# numishnik.net
KiCad netlist of a schematic drawn in EAGLE
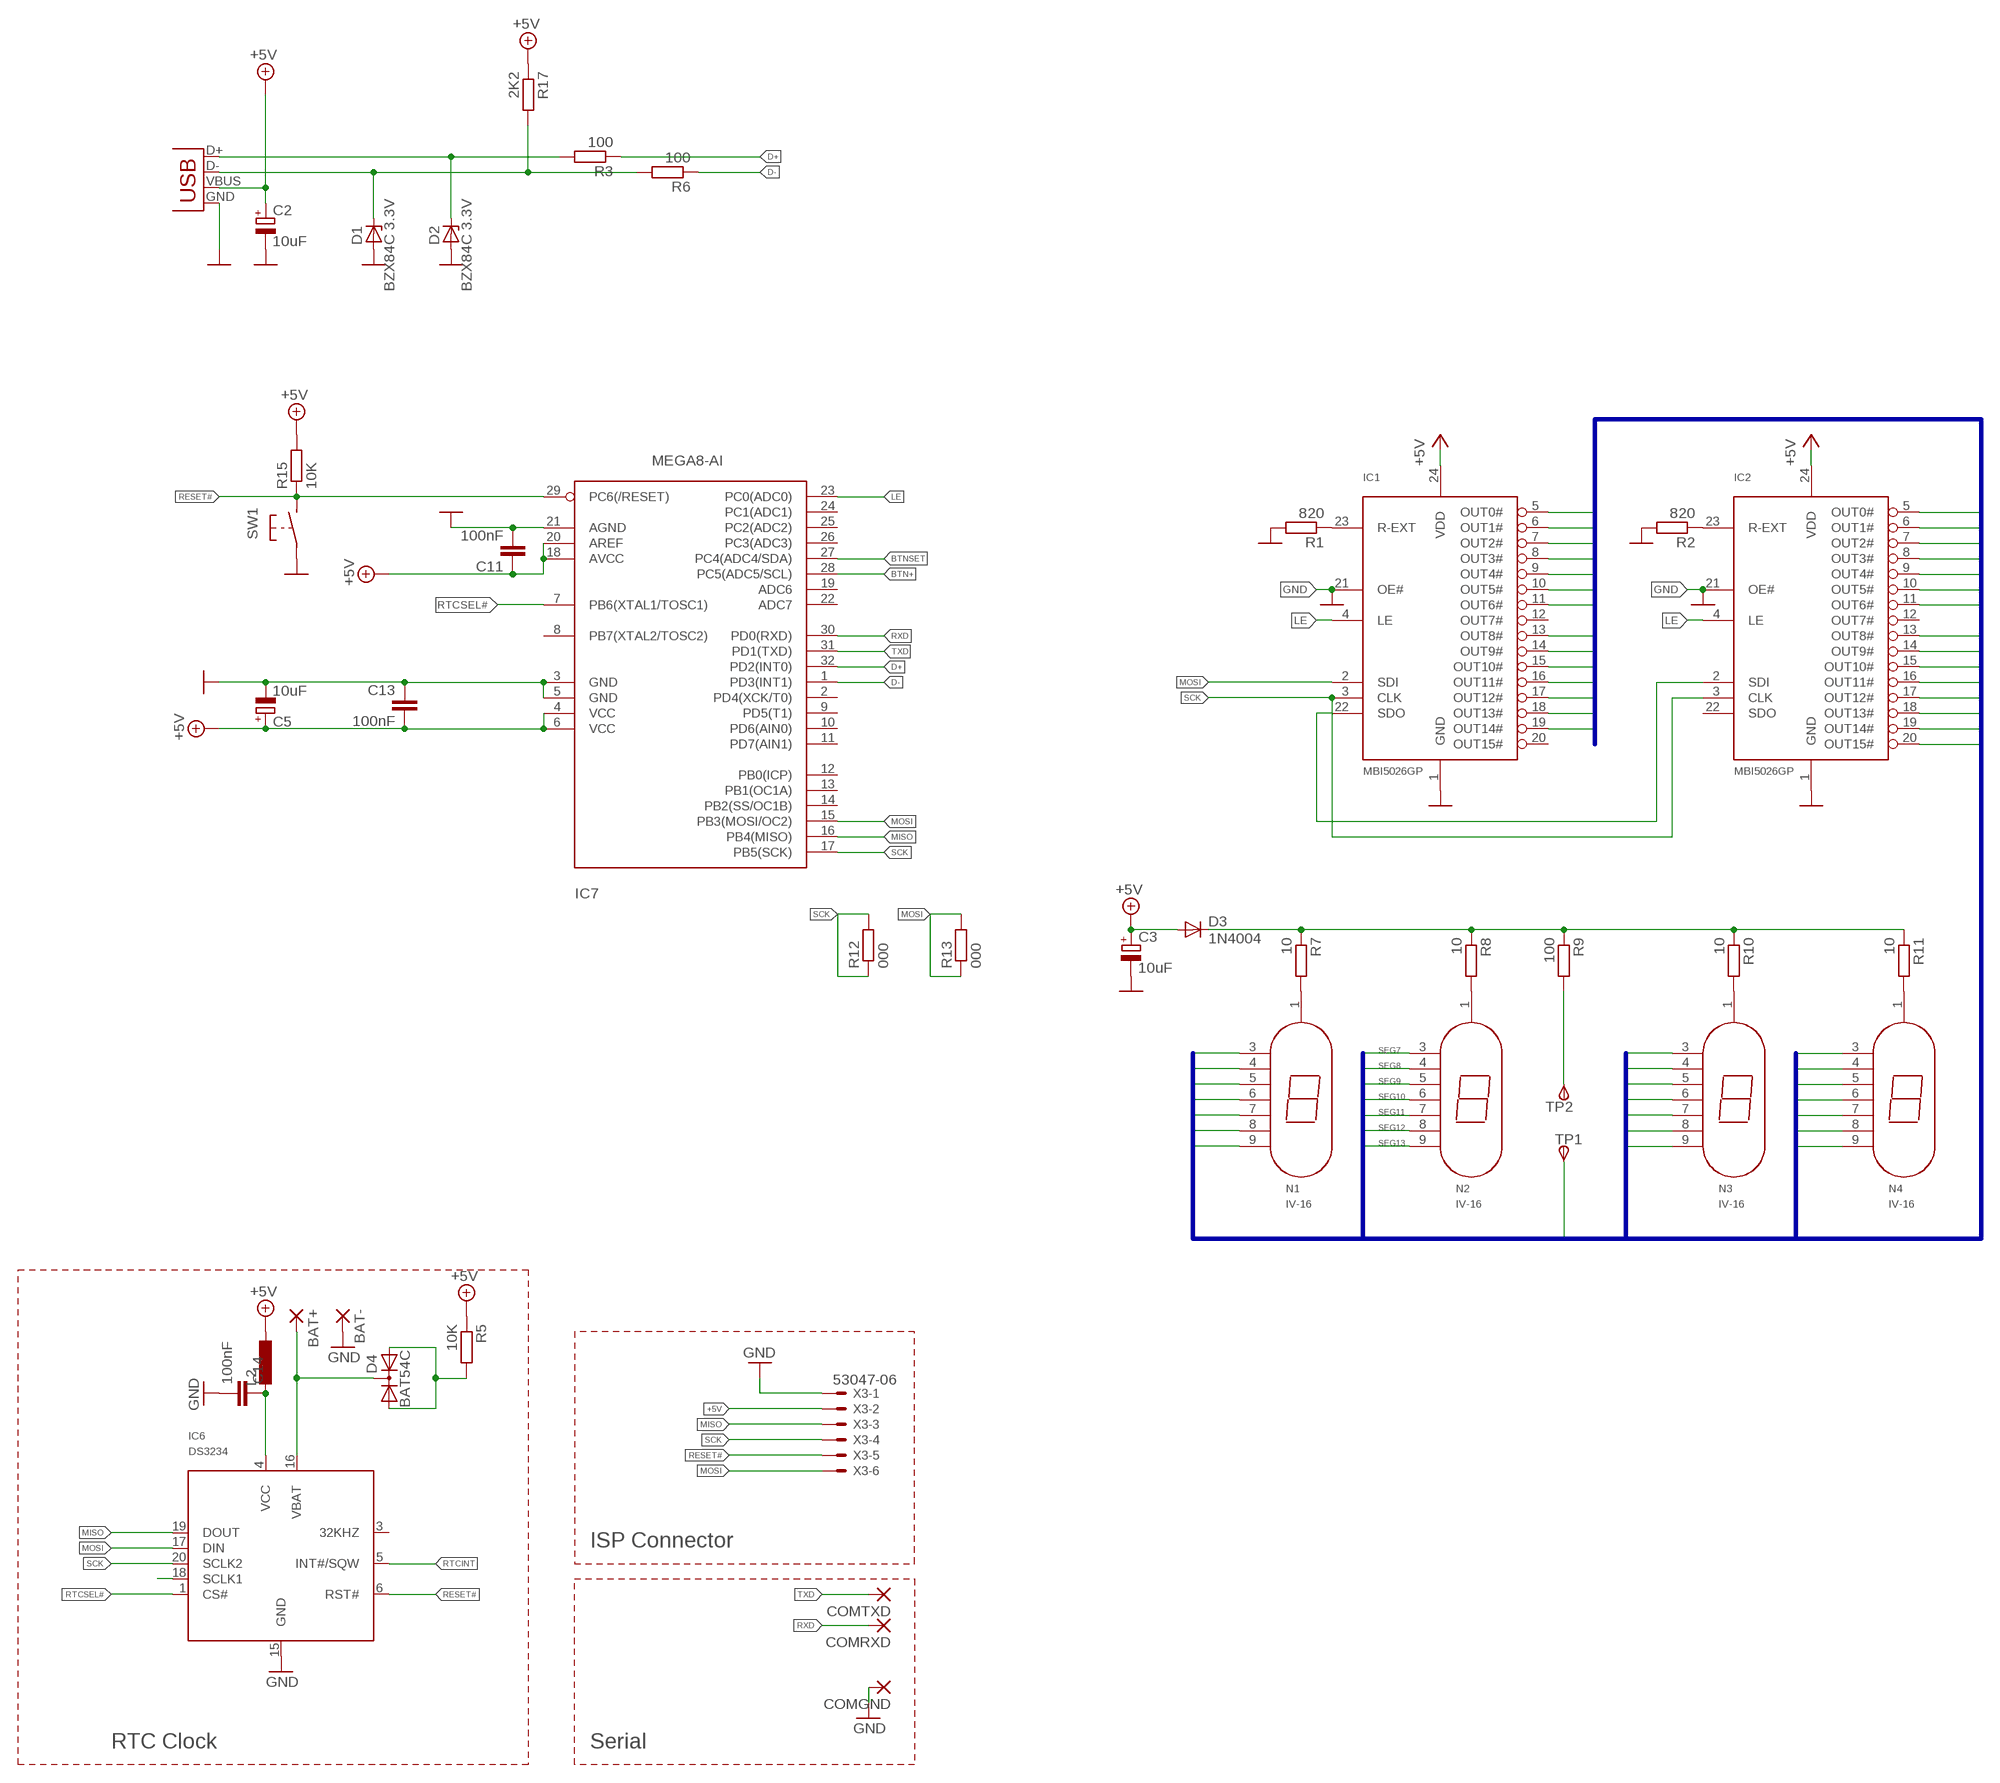
[diagram p0: schematic, sheet 1]

(export (version "E")
  (design (tool "Eeschema 10.0.6"))
  (components
    (comp (ref "BAT+")
      (value "1,6/0,8")
      (footprint "eagle-import:1,6_0,8")
      (libsource (lib "eagle-import") (part "1,6/0,8"))
    )
    (comp (ref "BAT-")
      (value "1,6/0,8")
      (footprint "eagle-import:1,6_0,8")
      (libsource (lib "eagle-import") (part "1,6/0,8"))
    )
    (comp (ref "C2")
      (value "10uF")
      (footprint "eagle-import:SMC_B")
      (libsource (lib "eagle-import") (part "CPOL-EUSMCB"))
    )
    (comp (ref "C3")
      (value "10uF")
      (footprint "eagle-import:SMC_B")
      (libsource (lib "eagle-import") (part "CPOL-EUSMCB"))
    )
    (comp (ref "C5")
      (value "10uF")
      (footprint "eagle-import:SMC_B")
      (libsource (lib "eagle-import") (part "CPOL-EUSMCB"))
    )
    (comp (ref "C11")
      (value "100nF")
      (footprint "eagle-import:C0603K")
      (libsource (lib "eagle-import") (part "C-EUC0603K"))
    )
    (comp (ref "C13")
      (value "100nF")
      (footprint "eagle-import:C0603K")
      (libsource (lib "eagle-import") (part "C-EUC0603K"))
    )
    (comp (ref "C14")
      (value "100nF")
      (footprint "eagle-import:C0603K")
      (libsource (lib "eagle-import") (part "C-EUC0603K"))
    )
    (comp (ref "COMGND")
      (value "1,6/0,8")
      (footprint "eagle-import:1,6_0,8")
      (libsource (lib "eagle-import") (part "1,6/0,8"))
    )
    (comp (ref "COMRXD")
      (value "1,6/0,8")
      (footprint "eagle-import:1,6_0,8")
      (libsource (lib "eagle-import") (part "1,6/0,8"))
    )
    (comp (ref "COMTXD")
      (value "1,6/0,8")
      (footprint "eagle-import:1,6_0,8")
      (libsource (lib "eagle-import") (part "1,6/0,8"))
    )
    (comp (ref "D1")
      (value "BZX84C 3.3V")
      (footprint "eagle-import:TO236")
      (libsource (lib "eagle-import") (part "BZX84CSMD"))
    )
    (comp (ref "D2")
      (value "BZX84C 3.3V")
      (footprint "eagle-import:TO236")
      (libsource (lib "eagle-import") (part "BZX84CSMD"))
    )
    (comp (ref "D3")
      (value "1N4004")
      (footprint "eagle-import:DO41-10")
      (libsource (lib "eagle-import") (part "1N4004"))
    )
    (comp (ref "D4")
      (value "BAT54C")
      (footprint "eagle-import:SOT23")
      (libsource (lib "eagle-import") (part "DIODE-2AC|CASOT23"))
    )
    (comp (ref "IC1")
      (value "MBI5026GP")
      (footprint "eagle-import:SSOP24-150")
      (libsource (lib "eagle-import") (part "MBI5026GP"))
    )
    (comp (ref "IC2")
      (value "MBI5026GP")
      (footprint "eagle-import:SSOP24-150")
      (libsource (lib "eagle-import") (part "MBI5026GP"))
    )
    (comp (ref "IC6")
      (value "DS3234")
      (footprint "eagle-import:SO-20DW")
      (libsource (lib "eagle-import") (part "DS3234"))
    )
    (comp (ref "IC7")
      (value "MEGA8-AI")
      (footprint "eagle-import:TQFP32-08")
      (libsource (lib "eagle-import") (part "MEGA8-AI"))
    )
    (comp (ref "L2")
      (value "L-EUL3230M")
      (footprint "eagle-import:L3230M")
      (libsource (lib "eagle-import") (part "L-EUL3230M"))
    )
    (comp (ref "N1")
      (value "IV-16")
      (footprint "eagle-import:IV-16")
      (libsource (lib "eagle-import") (part "IV-16"))
    )
    (comp (ref "N2")
      (value "IV-16")
      (footprint "eagle-import:IV-16")
      (libsource (lib "eagle-import") (part "IV-16"))
    )
    (comp (ref "N3")
      (value "IV-16")
      (footprint "eagle-import:IV-16")
      (libsource (lib "eagle-import") (part "IV-16"))
    )
    (comp (ref "N4")
      (value "IV-16")
      (footprint "eagle-import:IV-16")
      (libsource (lib "eagle-import") (part "IV-16"))
    )
    (comp (ref "R1")
      (value "820")
      (footprint "eagle-import:R0805-SVO")
      (libsource (lib "eagle-import") (part "R-EU_R0805S"))
    )
    (comp (ref "R2")
      (value "820")
      (footprint "eagle-import:R0805-SVO")
      (libsource (lib "eagle-import") (part "R-EU_R0805S"))
    )
    (comp (ref "R3")
      (value "100")
      (footprint "eagle-import:R0805-SVO")
      (libsource (lib "eagle-import") (part "R-EU_R0805S"))
    )
    (comp (ref "R5")
      (value "10K")
      (footprint "eagle-import:R0805-SVO")
      (libsource (lib "eagle-import") (part "R-EU_R0805S"))
    )
    (comp (ref "R6")
      (value "100")
      (footprint "eagle-import:R0805-SVO")
      (libsource (lib "eagle-import") (part "R-EU_R0805S"))
    )
    (comp (ref "R7")
      (value "10")
      (footprint "eagle-import:R0805-SVO")
      (libsource (lib "eagle-import") (part "R-EU_R0805S"))
    )
    (comp (ref "R8")
      (value "10")
      (footprint "eagle-import:R0805-SVO")
      (libsource (lib "eagle-import") (part "R-EU_R0805S"))
    )
    (comp (ref "R9")
      (value "100")
      (footprint "eagle-import:R0805-SVO")
      (libsource (lib "eagle-import") (part "R-EU_R0805S"))
    )
    (comp (ref "R10")
      (value "10")
      (footprint "eagle-import:R0805-SVO")
      (libsource (lib "eagle-import") (part "R-EU_R0805S"))
    )
    (comp (ref "R11")
      (value "10")
      (footprint "eagle-import:R0805-SVO")
      (libsource (lib "eagle-import") (part "R-EU_R0805S"))
    )
    (comp (ref "R12")
      (value "000")
      (footprint "eagle-import:R0805-SVO")
      (libsource (lib "eagle-import") (part "R-EU_R0805S"))
    )
    (comp (ref "R13")
      (value "000")
      (footprint "eagle-import:R0805-SVO")
      (libsource (lib "eagle-import") (part "R-EU_R0805S"))
    )
    (comp (ref "R15")
      (value "10K")
      (footprint "eagle-import:R0805-SVO")
      (libsource (lib "eagle-import") (part "R-EU_R0805S"))
    )
    (comp (ref "R17")
      (value "2K2")
      (footprint "eagle-import:R0805-SVO")
      (libsource (lib "eagle-import") (part "R-EU_R0805S"))
    )
    (comp (ref "SW1")
      (value "BUTTON-IT_1181")
      (footprint "eagle-import:SW_IT1181")
      (libsource (lib "eagle-import") (part "BUTTON-IT_1181"))
    )
    (comp (ref "TP1")
      (value "TPSPAD1-13")
      (footprint "eagle-import:P1-13")
      (libsource (lib "eagle-import") (part "TPSPAD1-13"))
    )
    (comp (ref "TP2")
      (value "TPSPAD1-13")
      (footprint "eagle-import:P1-13")
      (libsource (lib "eagle-import") (part "TPSPAD1-13"))
    )
    (comp (ref "X1")
      (value "USB-MICROB")
      (footprint "eagle-import:USB-MICROB")
      (libsource (lib "eagle-import") (part "USB-MICROB"))
    )
    (comp (ref "X3")
      (value "53047-06")
      (footprint "eagle-import:53047-06")
      (libsource (lib "eagle-import") (part "53?-06047"))
    )
  )
  (nets
    (net (code "1") (name "+5V") (class "Default")
      (node (ref "C11") (pin "1") (pinfunction "1_1") (pintype "passive"))
      (node (ref "C13") (pin "2") (pinfunction "2_2") (pintype "passive"))
      (node (ref "C2") (pin "+") (pinfunction "+_+") (pintype "passive"))
      (node (ref "C3") (pin "+") (pinfunction "+_+") (pintype "passive"))
      (node (ref "C5") (pin "+") (pinfunction "+_+") (pintype "passive"))
      (node (ref "D3") (pin "A") (pinfunction "A_A") (pintype "passive"))
      (node (ref "IC1") (pin "24") (pinfunction "VDD_24") (pintype "power_in"))
      (node (ref "IC2") (pin "24") (pinfunction "VDD_24") (pintype "power_in"))
      (node (ref "IC7") (pin "18") (pinfunction "AVCC_18") (pintype "power_in"))
      (node (ref "IC7") (pin "20") (pinfunction "AREF_20") (pintype "passive"))
      (node (ref "IC7") (pin "4") (pinfunction "VCC_4") (pintype "power_in"))
      (node (ref "IC7") (pin "6") (pinfunction "VCC_6") (pintype "power_in"))
      (node (ref "L2") (pin "1") (pinfunction "1_1") (pintype "passive"))
      (node (ref "R15") (pin "2") (pinfunction "2_2") (pintype "passive"))
      (node (ref "R17") (pin "1") (pinfunction "1_1") (pintype "passive"))
      (node (ref "R5") (pin "1") (pinfunction "1_1") (pintype "passive"))
      (node (ref "X1") (pin "VBUS") (pinfunction "VBUS_VBUS") (pintype "bidirectional"))
      (node (ref "X3") (pin "2") (pinfunction "S_2") (pintype "passive"))
    )
    (net (code "2") (name "/DOT") (class "Default")
      (node (ref "IC2") (pin "20") (pinfunction "OUT15#_20") (pintype "bidirectional"))
      (node (ref "TP1") (pin "1") (pinfunction "PP_1") (pintype "input"))
    )
    (net (code "3") (name "/SEG0") (class "Default")
      (node (ref "IC1") (pin "11") (pinfunction "OUT6#_11") (pintype "bidirectional"))
      (node (ref "N1") (pin "3") (pinfunction "2_3") (pintype "bidirectional"))
    )
    (net (code "4") (name "/SEG1") (class "Default")
      (node (ref "IC1") (pin "10") (pinfunction "OUT5#_10") (pintype "bidirectional"))
      (node (ref "N1") (pin "4") (pinfunction "3_4") (pintype "bidirectional"))
    )
    (net (code "5") (name "/SEG2") (class "Default")
      (node (ref "IC1") (pin "9") (pinfunction "OUT4#_9") (pintype "bidirectional"))
      (node (ref "N1") (pin "5") (pinfunction "4_5") (pintype "bidirectional"))
    )
    (net (code "6") (name "/SEG3") (class "Default")
      (node (ref "IC1") (pin "8") (pinfunction "OUT3#_8") (pintype "bidirectional"))
      (node (ref "N1") (pin "6") (pinfunction "5_6") (pintype "bidirectional"))
    )
    (net (code "7") (name "/SEG4") (class "Default")
      (node (ref "IC1") (pin "7") (pinfunction "OUT2#_7") (pintype "bidirectional"))
      (node (ref "N1") (pin "7") (pinfunction "6_7") (pintype "bidirectional"))
    )
    (net (code "8") (name "/SEG5") (class "Default")
      (node (ref "IC1") (pin "6") (pinfunction "OUT1#_6") (pintype "bidirectional"))
      (node (ref "N1") (pin "8") (pinfunction "7_8") (pintype "bidirectional"))
    )
    (net (code "9") (name "/SEG6") (class "Default")
      (node (ref "IC1") (pin "5") (pinfunction "OUT0#_5") (pintype "bidirectional"))
      (node (ref "N1") (pin "9") (pinfunction "8_9") (pintype "bidirectional"))
    )
    (net (code "10") (name "/SEG7") (class "Default")
      (node (ref "IC1") (pin "19") (pinfunction "OUT14#_19") (pintype "bidirectional"))
      (node (ref "N2") (pin "3") (pinfunction "2_3") (pintype "bidirectional"))
    )
    (net (code "11") (name "/SEG8") (class "Default")
      (node (ref "IC1") (pin "18") (pinfunction "OUT13#_18") (pintype "bidirectional"))
      (node (ref "N2") (pin "4") (pinfunction "3_4") (pintype "bidirectional"))
    )
    (net (code "12") (name "/SEG9") (class "Default")
      (node (ref "IC1") (pin "17") (pinfunction "OUT12#_17") (pintype "bidirectional"))
      (node (ref "N2") (pin "5") (pinfunction "4_5") (pintype "bidirectional"))
    )
    (net (code "13") (name "/SEG10") (class "Default")
      (node (ref "IC1") (pin "16") (pinfunction "OUT11#_16") (pintype "bidirectional"))
      (node (ref "N2") (pin "6") (pinfunction "5_6") (pintype "bidirectional"))
    )
    (net (code "14") (name "/SEG11") (class "Default")
      (node (ref "IC1") (pin "15") (pinfunction "OUT10#_15") (pintype "bidirectional"))
      (node (ref "N2") (pin "7") (pinfunction "6_7") (pintype "bidirectional"))
    )
    (net (code "15") (name "/SEG12") (class "Default")
      (node (ref "IC1") (pin "14") (pinfunction "OUT9#_14") (pintype "bidirectional"))
      (node (ref "N2") (pin "8") (pinfunction "7_8") (pintype "bidirectional"))
    )
    (net (code "16") (name "/SEG13") (class "Default")
      (node (ref "IC1") (pin "13") (pinfunction "OUT8#_13") (pintype "bidirectional"))
      (node (ref "N2") (pin "9") (pinfunction "8_9") (pintype "bidirectional"))
    )
    (net (code "17") (name "/SEG14") (class "Default")
      (node (ref "IC2") (pin "11") (pinfunction "OUT6#_11") (pintype "bidirectional"))
      (node (ref "N3") (pin "3") (pinfunction "2_3") (pintype "bidirectional"))
    )
    (net (code "18") (name "/SEG15") (class "Default")
      (node (ref "IC2") (pin "10") (pinfunction "OUT5#_10") (pintype "bidirectional"))
      (node (ref "N3") (pin "4") (pinfunction "3_4") (pintype "bidirectional"))
    )
    (net (code "19") (name "/SEG16") (class "Default")
      (node (ref "IC2") (pin "9") (pinfunction "OUT4#_9") (pintype "bidirectional"))
      (node (ref "N3") (pin "5") (pinfunction "4_5") (pintype "bidirectional"))
    )
    (net (code "20") (name "/SEG17") (class "Default")
      (node (ref "IC2") (pin "8") (pinfunction "OUT3#_8") (pintype "bidirectional"))
      (node (ref "N3") (pin "6") (pinfunction "5_6") (pintype "bidirectional"))
    )
    (net (code "21") (name "/SEG18") (class "Default")
      (node (ref "IC2") (pin "7") (pinfunction "OUT2#_7") (pintype "bidirectional"))
      (node (ref "N3") (pin "7") (pinfunction "6_7") (pintype "bidirectional"))
    )
    (net (code "22") (name "/SEG19") (class "Default")
      (node (ref "IC2") (pin "6") (pinfunction "OUT1#_6") (pintype "bidirectional"))
      (node (ref "N3") (pin "8") (pinfunction "7_8") (pintype "bidirectional"))
    )
    (net (code "23") (name "/SEG20") (class "Default")
      (node (ref "IC2") (pin "5") (pinfunction "OUT0#_5") (pintype "bidirectional"))
      (node (ref "N3") (pin "9") (pinfunction "8_9") (pintype "bidirectional"))
    )
    (net (code "24") (name "/SEG21") (class "Default")
      (node (ref "IC2") (pin "19") (pinfunction "OUT14#_19") (pintype "bidirectional"))
      (node (ref "N4") (pin "3") (pinfunction "2_3") (pintype "bidirectional"))
    )
    (net (code "25") (name "/SEG22") (class "Default")
      (node (ref "IC2") (pin "18") (pinfunction "OUT13#_18") (pintype "bidirectional"))
      (node (ref "N4") (pin "4") (pinfunction "3_4") (pintype "bidirectional"))
    )
    (net (code "26") (name "/SEG23") (class "Default")
      (node (ref "IC2") (pin "17") (pinfunction "OUT12#_17") (pintype "bidirectional"))
      (node (ref "N4") (pin "5") (pinfunction "4_5") (pintype "bidirectional"))
    )
    (net (code "27") (name "/SEG24") (class "Default")
      (node (ref "IC2") (pin "16") (pinfunction "OUT11#_16") (pintype "bidirectional"))
      (node (ref "N4") (pin "6") (pinfunction "5_6") (pintype "bidirectional"))
    )
    (net (code "28") (name "/SEG25") (class "Default")
      (node (ref "IC2") (pin "15") (pinfunction "OUT10#_15") (pintype "bidirectional"))
      (node (ref "N4") (pin "7") (pinfunction "6_7") (pintype "bidirectional"))
    )
    (net (code "29") (name "/SEG26") (class "Default")
      (node (ref "IC2") (pin "14") (pinfunction "OUT9#_14") (pintype "bidirectional"))
      (node (ref "N4") (pin "8") (pinfunction "7_8") (pintype "bidirectional"))
    )
    (net (code "30") (name "/SEG27") (class "Default")
      (node (ref "IC2") (pin "13") (pinfunction "OUT8#_13") (pintype "bidirectional"))
      (node (ref "N4") (pin "9") (pinfunction "8_9") (pintype "bidirectional"))
    )
    (net (code "31") (name "BTN+") (class "Default")
      (node (ref "IC7") (pin "28") (pinfunction "PC5(ADC5/SCL)_28") (pintype "bidirectional"))
    )
    (net (code "32") (name "BTNSET") (class "Default")
      (node (ref "IC7") (pin "27") (pinfunction "PC4(ADC4/SDA)_27") (pintype "bidirectional"))
    )
    (net (code "33") (name "D+") (class "Default")
      (node (ref "IC7") (pin "32") (pinfunction "PD2(INT0)_32") (pintype "bidirectional"))
      (node (ref "R3") (pin "1") (pinfunction "1_1") (pintype "passive"))
    )
    (net (code "34") (name "D-") (class "Default")
      (node (ref "IC7") (pin "1") (pinfunction "PD3(INT1)_1") (pintype "bidirectional"))
      (node (ref "R6") (pin "1") (pinfunction "1_1") (pintype "passive"))
    )
    (net (code "35") (name "GND") (class "Default")
      (node (ref "BAT-") (pin "1") (pinfunction "P_1") (pintype "passive"))
      (node (ref "C11") (pin "2") (pinfunction "2_2") (pintype "passive"))
      (node (ref "C13") (pin "1") (pinfunction "1_1") (pintype "passive"))
      (node (ref "C14") (pin "2") (pinfunction "2_2") (pintype "passive"))
      (node (ref "C2") (pin "-") (pinfunction "-_-") (pintype "passive"))
      (node (ref "C3") (pin "-") (pinfunction "-_-") (pintype "passive"))
      (node (ref "C5") (pin "-") (pinfunction "-_-") (pintype "passive"))
      (node (ref "COMGND") (pin "1") (pinfunction "P_1") (pintype "passive"))
      (node (ref "D1") (pin "A") (pinfunction "A_A") (pintype "passive"))
      (node (ref "D2") (pin "A") (pinfunction "A_A") (pintype "passive"))
      (node (ref "IC1") (pin "1") (pinfunction "GND_1") (pintype "power_in"))
      (node (ref "IC1") (pin "21") (pinfunction "OE#_21") (pintype "bidirectional"))
      (node (ref "IC2") (pin "1") (pinfunction "GND_1") (pintype "power_in"))
      (node (ref "IC2") (pin "21") (pinfunction "OE#_21") (pintype "bidirectional"))
      (node (ref "IC6") (pin "15") (pinfunction "GND_15") (pintype "bidirectional"))
      (node (ref "IC7") (pin "21") (pinfunction "AGND_21") (pintype "power_in"))
      (node (ref "IC7") (pin "3") (pinfunction "GND_3") (pintype "power_in"))
      (node (ref "IC7") (pin "5") (pinfunction "GND_5") (pintype "power_in"))
      (node (ref "R1") (pin "2") (pinfunction "2_2") (pintype "passive"))
      (node (ref "R2") (pin "2") (pinfunction "2_2") (pintype "passive"))
      (node (ref "SW1") (pin "P$1") (pinfunction "P1_P$1") (pintype "passive"))
      (node (ref "X1") (pin "GND") (pinfunction "GND_GND") (pintype "bidirectional"))
      (node (ref "X3") (pin "1") (pinfunction "S_1") (pintype "passive"))
    )
    (net (code "36") (name "LE") (class "Default")
      (node (ref "IC1") (pin "4") (pinfunction "LE_4") (pintype "bidirectional"))
      (node (ref "IC2") (pin "4") (pinfunction "LE_4") (pintype "bidirectional"))
      (node (ref "IC7") (pin "23") (pinfunction "PC0(ADC0)_23") (pintype "bidirectional"))
    )
    (net (code "37") (name "MISO") (class "Default")
      (node (ref "IC6") (pin "19") (pinfunction "DOUT_19") (pintype "bidirectional"))
      (node (ref "IC7") (pin "16") (pinfunction "PB4(MISO)_16") (pintype "bidirectional"))
      (node (ref "X3") (pin "3") (pinfunction "S_3") (pintype "passive"))
    )
    (net (code "38") (name "MOSI") (class "Default")
      (node (ref "IC1") (pin "2") (pinfunction "SDI_2") (pintype "bidirectional"))
      (node (ref "IC6") (pin "17") (pinfunction "DIN_17") (pintype "bidirectional"))
      (node (ref "IC7") (pin "15") (pinfunction "PB3(MOSI/OC2)_15") (pintype "bidirectional"))
      (node (ref "R13") (pin "1") (pinfunction "1_1") (pintype "passive"))
      (node (ref "R13") (pin "2") (pinfunction "2_2") (pintype "passive"))
      (node (ref "X3") (pin "6") (pinfunction "S_6") (pintype "passive"))
    )
    (net (code "39") (name "Net-(BAT+-P)") (class "Default")
      (node (ref "BAT+") (pin "1") (pinfunction "P_1") (pintype "passive"))
      (node (ref "D4") (pin "3") (pinfunction "C_3") (pintype "passive"))
      (node (ref "IC6") (pin "16") (pinfunction "VBAT_16") (pintype "bidirectional"))
    )
    (net (code "40") (name "Net-(D1-PadC)") (class "Default")
      (node (ref "D1") (pin "C") (pinfunction "C_C") (pintype "passive"))
      (node (ref "R17") (pin "2") (pinfunction "2_2") (pintype "passive"))
      (node (ref "R6") (pin "2") (pinfunction "2_2") (pintype "passive"))
      (node (ref "X1") (pin "D-") (pinfunction "D-_D-") (pintype "bidirectional"))
    )
    (net (code "41") (name "Net-(D2-PadC)") (class "Default")
      (node (ref "D2") (pin "C") (pinfunction "C_C") (pintype "passive"))
      (node (ref "R3") (pin "2") (pinfunction "2_2") (pintype "passive"))
      (node (ref "X1") (pin "D+") (pinfunction "D+_D+") (pintype "bidirectional"))
    )
    (net (code "42") (name "Net-(D3-PadC)") (class "Default")
      (node (ref "D3") (pin "C") (pinfunction "C_C") (pintype "passive"))
      (node (ref "R10") (pin "1") (pinfunction "1_1") (pintype "passive"))
      (node (ref "R11") (pin "1") (pinfunction "1_1") (pintype "passive"))
      (node (ref "R7") (pin "1") (pinfunction "1_1") (pintype "passive"))
      (node (ref "R8") (pin "1") (pinfunction "1_1") (pintype "passive"))
      (node (ref "R9") (pin "1") (pinfunction "1_1") (pintype "passive"))
    )
    (net (code "43") (name "Net-(D4-A1)") (class "Default")
      (node (ref "D4") (pin "1") (pinfunction "A1_1") (pintype "passive"))
      (node (ref "D4") (pin "2") (pinfunction "A2_2") (pintype "passive"))
      (node (ref "R5") (pin "2") (pinfunction "2_2") (pintype "passive"))
    )
    (net (code "44") (name "Net-(IC1-R-EXT)") (class "Default")
      (node (ref "IC1") (pin "23") (pinfunction "R-EXT_23") (pintype "bidirectional"))
      (node (ref "R1") (pin "1") (pinfunction "1_1") (pintype "passive"))
    )
    (net (code "45") (name "Net-(IC1-SDO)") (class "Default")
      (node (ref "IC1") (pin "22") (pinfunction "SDO_22") (pintype "bidirectional"))
      (node (ref "IC2") (pin "2") (pinfunction "SDI_2") (pintype "bidirectional"))
    )
    (net (code "46") (name "Net-(IC2-R-EXT)") (class "Default")
      (node (ref "IC2") (pin "23") (pinfunction "R-EXT_23") (pintype "bidirectional"))
      (node (ref "R2") (pin "1") (pinfunction "1_1") (pintype "passive"))
    )
    (net (code "47") (name "Net-(IC6-VCC)") (class "Default")
      (node (ref "C14") (pin "1") (pinfunction "1_1") (pintype "passive"))
      (node (ref "IC6") (pin "4") (pinfunction "VCC_4") (pintype "bidirectional"))
      (node (ref "L2") (pin "2") (pinfunction "2_2") (pintype "passive"))
    )
    (net (code "48") (name "Net-(N1-Pad1)") (class "Default")
      (node (ref "N1") (pin "1") (pinfunction "1_1") (pintype "bidirectional"))
      (node (ref "R7") (pin "2") (pinfunction "2_2") (pintype "passive"))
    )
    (net (code "49") (name "Net-(N2-Pad1)") (class "Default")
      (node (ref "N2") (pin "1") (pinfunction "1_1") (pintype "bidirectional"))
      (node (ref "R8") (pin "2") (pinfunction "2_2") (pintype "passive"))
    )
    (net (code "50") (name "Net-(N3-Pad1)") (class "Default")
      (node (ref "N3") (pin "1") (pinfunction "1_1") (pintype "bidirectional"))
      (node (ref "R10") (pin "2") (pinfunction "2_2") (pintype "passive"))
    )
    (net (code "51") (name "Net-(N4-Pad1)") (class "Default")
      (node (ref "N4") (pin "1") (pinfunction "1_1") (pintype "bidirectional"))
      (node (ref "R11") (pin "2") (pinfunction "2_2") (pintype "passive"))
    )
    (net (code "52") (name "Net-(TP2-PP)") (class "Default")
      (node (ref "R9") (pin "2") (pinfunction "2_2") (pintype "passive"))
      (node (ref "TP2") (pin "1") (pinfunction "PP_1") (pintype "input"))
    )
    (net (code "53") (name "RESET#") (class "Default")
      (node (ref "IC6") (pin "6") (pinfunction "RST#_6") (pintype "bidirectional"))
      (node (ref "IC7") (pin "29") (pinfunction "PC6(/RESET)_29") (pintype "bidirectional"))
      (node (ref "R15") (pin "1") (pinfunction "1_1") (pintype "passive"))
      (node (ref "SW1") (pin "P$2") (pinfunction "P2_P$2") (pintype "passive"))
      (node (ref "X3") (pin "5") (pinfunction "S_5") (pintype "passive"))
    )
    (net (code "54") (name "RTCINT") (class "Default")
      (node (ref "IC6") (pin "5") (pinfunction "INT#/SQW_5") (pintype "bidirectional"))
    )
    (net (code "55") (name "RTCSEL#") (class "Default")
      (node (ref "IC6") (pin "1") (pinfunction "CS#_1") (pintype "bidirectional"))
      (node (ref "IC7") (pin "7") (pinfunction "PB6(XTAL1/TOSC1)_7") (pintype "bidirectional"))
    )
    (net (code "56") (name "RXD") (class "Default")
      (node (ref "COMRXD") (pin "1") (pinfunction "P_1") (pintype "passive"))
      (node (ref "IC7") (pin "30") (pinfunction "PD0(RXD)_30") (pintype "bidirectional"))
    )
    (net (code "57") (name "SCK") (class "Default")
      (node (ref "IC1") (pin "3") (pinfunction "CLK_3") (pintype "bidirectional"))
      (node (ref "IC2") (pin "3") (pinfunction "CLK_3") (pintype "bidirectional"))
      (node (ref "IC6") (pin "20") (pinfunction "SCLK2_20") (pintype "bidirectional"))
      (node (ref "IC7") (pin "17") (pinfunction "PB5(SCK)_17") (pintype "bidirectional"))
      (node (ref "R12") (pin "1") (pinfunction "1_1") (pintype "passive"))
      (node (ref "R12") (pin "2") (pinfunction "2_2") (pintype "passive"))
      (node (ref "X3") (pin "4") (pinfunction "S_4") (pintype "passive"))
    )
    (net (code "58") (name "TXD") (class "Default")
      (node (ref "COMTXD") (pin "1") (pinfunction "P_1") (pintype "passive"))
      (node (ref "IC7") (pin "31") (pinfunction "PD1(TXD)_31") (pintype "bidirectional"))
    )
    (net (code "59") (name "unconnected-(IC1-OUT7#-Pad12)") (class "Default")
      (node (ref "IC1") (pin "12") (pinfunction "OUT7#_12") (pintype "bidirectional"))
    )
    (net (code "60") (name "unconnected-(IC1-OUT15#-Pad20)") (class "Default")
      (node (ref "IC1") (pin "20") (pinfunction "OUT15#_20") (pintype "bidirectional"))
    )
    (net (code "61") (name "unconnected-(IC2-OUT7#-Pad12)") (class "Default")
      (node (ref "IC2") (pin "12") (pinfunction "OUT7#_12") (pintype "bidirectional"))
    )
    (net (code "62") (name "unconnected-(IC2-SDO-Pad22)") (class "Default")
      (node (ref "IC2") (pin "22") (pinfunction "SDO_22") (pintype "bidirectional"))
    )
    (net (code "63") (name "unconnected-(IC6-32KHZ-Pad3)") (class "Default")
      (node (ref "IC6") (pin "3") (pinfunction "32KHZ_3") (pintype "bidirectional"))
    )
    (net (code "64") (name "unconnected-(IC6-SCLK1-Pad18)") (class "Default")
      (node (ref "IC6") (pin "18") (pinfunction "SCLK1_18") (pintype "bidirectional"))
    )
    (net (code "65") (name "unconnected-(IC7-ADC6-Pad19)") (class "Default")
      (node (ref "IC7") (pin "19") (pinfunction "ADC6_19") (pintype "bidirectional"))
    )
    (net (code "66") (name "unconnected-(IC7-ADC7-Pad22)") (class "Default")
      (node (ref "IC7") (pin "22") (pinfunction "ADC7_22") (pintype "bidirectional"))
    )
    (net (code "67") (name "unconnected-(IC7-PB0(ICP)-Pad12)") (class "Default")
      (node (ref "IC7") (pin "12") (pinfunction "PB0(ICP)_12") (pintype "bidirectional"))
    )
    (net (code "68") (name "unconnected-(IC7-PB1(OC1A)-Pad13)") (class "Default")
      (node (ref "IC7") (pin "13") (pinfunction "PB1(OC1A)_13") (pintype "bidirectional"))
    )
    (net (code "69") (name "unconnected-(IC7-PB2(SS{slash}OC1B)-Pad14)") (class "Default")
      (node (ref "IC7") (pin "14") (pinfunction "PB2(SS/OC1B)_14") (pintype "bidirectional"))
    )
    (net (code "70") (name "unconnected-(IC7-PB7(XTAL2{slash}TOSC2)-Pad8)") (class "Default")
      (node (ref "IC7") (pin "8") (pinfunction "PB7(XTAL2/TOSC2)_8") (pintype "bidirectional"))
    )
    (net (code "71") (name "unconnected-(IC7-PC1(ADC1)-Pad24)") (class "Default")
      (node (ref "IC7") (pin "24") (pinfunction "PC1(ADC1)_24") (pintype "bidirectional"))
    )
    (net (code "72") (name "unconnected-(IC7-PC2(ADC2)-Pad25)") (class "Default")
      (node (ref "IC7") (pin "25") (pinfunction "PC2(ADC2)_25") (pintype "bidirectional"))
    )
    (net (code "73") (name "unconnected-(IC7-PC3(ADC3)-Pad26)") (class "Default")
      (node (ref "IC7") (pin "26") (pinfunction "PC3(ADC3)_26") (pintype "bidirectional"))
    )
    (net (code "74") (name "unconnected-(IC7-PD4(XCK{slash}T0)-Pad2)") (class "Default")
      (node (ref "IC7") (pin "2") (pinfunction "PD4(XCK/T0)_2") (pintype "bidirectional"))
    )
    (net (code "75") (name "unconnected-(IC7-PD5(T1)-Pad9)") (class "Default")
      (node (ref "IC7") (pin "9") (pinfunction "PD5(T1)_9") (pintype "bidirectional"))
    )
    (net (code "76") (name "unconnected-(IC7-PD6(AIN0)-Pad10)") (class "Default")
      (node (ref "IC7") (pin "10") (pinfunction "PD6(AIN0)_10") (pintype "bidirectional"))
    )
    (net (code "77") (name "unconnected-(IC7-PD7(AIN1)-Pad11)") (class "Default")
      (node (ref "IC7") (pin "11") (pinfunction "PD7(AIN1)_11") (pintype "bidirectional"))
    )
  )
)
